# SimpleCircuit.net
KiCad netlist of a schematic drawn in EAGLE
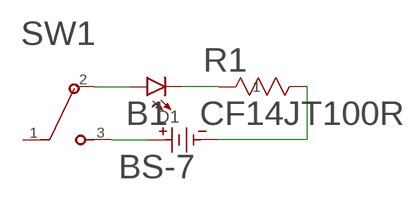
[diagram p0: schematic, sheet 1]

(export (version "E")
  (design (tool "Eeschema 10.0.6"))
  (components
    (comp (ref "B1")
      (value "BS-7")
      (footprint "eagle-import:BS-7_MPD")
      (fields (field (name "COPYRIGHT") "Copyright (C) 2018 Accelerated Designs. All rights reserved"))
      (libsource (lib "eagle-import") (part "BS-7"))
    )
    (comp (ref "D1")
      (value "LED3MM")
      (footprint "eagle-import:LED_3MM")
      (libsource (lib "eagle-import") (part "LED3MM"))
    )
    (comp (ref "R1")
      (value "CF14JT100R")
      (footprint "eagle-import:STA_CF14_STP")
      (libsource (lib "eagle-import") (part "CF14JT100R"))
    )
    (comp (ref "SW1")
      (value "EG1218")
      (footprint "eagle-import:SW_1218_EWI")
      (fields (field (name "COPYRIGHT") "Copyright (C) 2018 Accelerated Designs. All rights reserved"))
      (libsource (lib "eagle-import") (part "EG1218"))
    )
  )
  (nets
    (net (code "1") (name "Net-(B1-Pad1)") (class "Default")
      (node (ref "B1") (pin "1") (pinfunction "1_1") (pintype "passive"))
      (node (ref "R1") (pin "2") (pinfunction "2_2") (pintype "passive"))
    )
    (net (code "2") (name "Net-(B1-Pad2)") (class "Default")
      (node (ref "B1") (pin "2") (pinfunction "2_2") (pintype "passive"))
      (node (ref "SW1") (pin "3") (pinfunction "3_3") (pintype "passive"))
    )
    (net (code "3") (name "Net-(D1-C)") (class "Default")
      (node (ref "D1") (pin "K") (pinfunction "C_K") (pintype "passive"))
      (node (ref "R1") (pin "1") (pinfunction "1_1") (pintype "passive"))
    )
    (net (code "4") (name "Net-(D1-PadA)") (class "Default")
      (node (ref "D1") (pin "A") (pinfunction "A_A") (pintype "passive"))
      (node (ref "SW1") (pin "2") (pinfunction "2_2") (pintype "passive"))
    )
    (net (code "5") (name "unconnected-(SW1-Pad1)") (class "Default")
      (node (ref "SW1") (pin "1") (pinfunction "1_1") (pintype "passive"))
    )
  )
)
